# AUX_power_board_V3_2.net
KiCad netlist of a schematic drawn in EAGLE
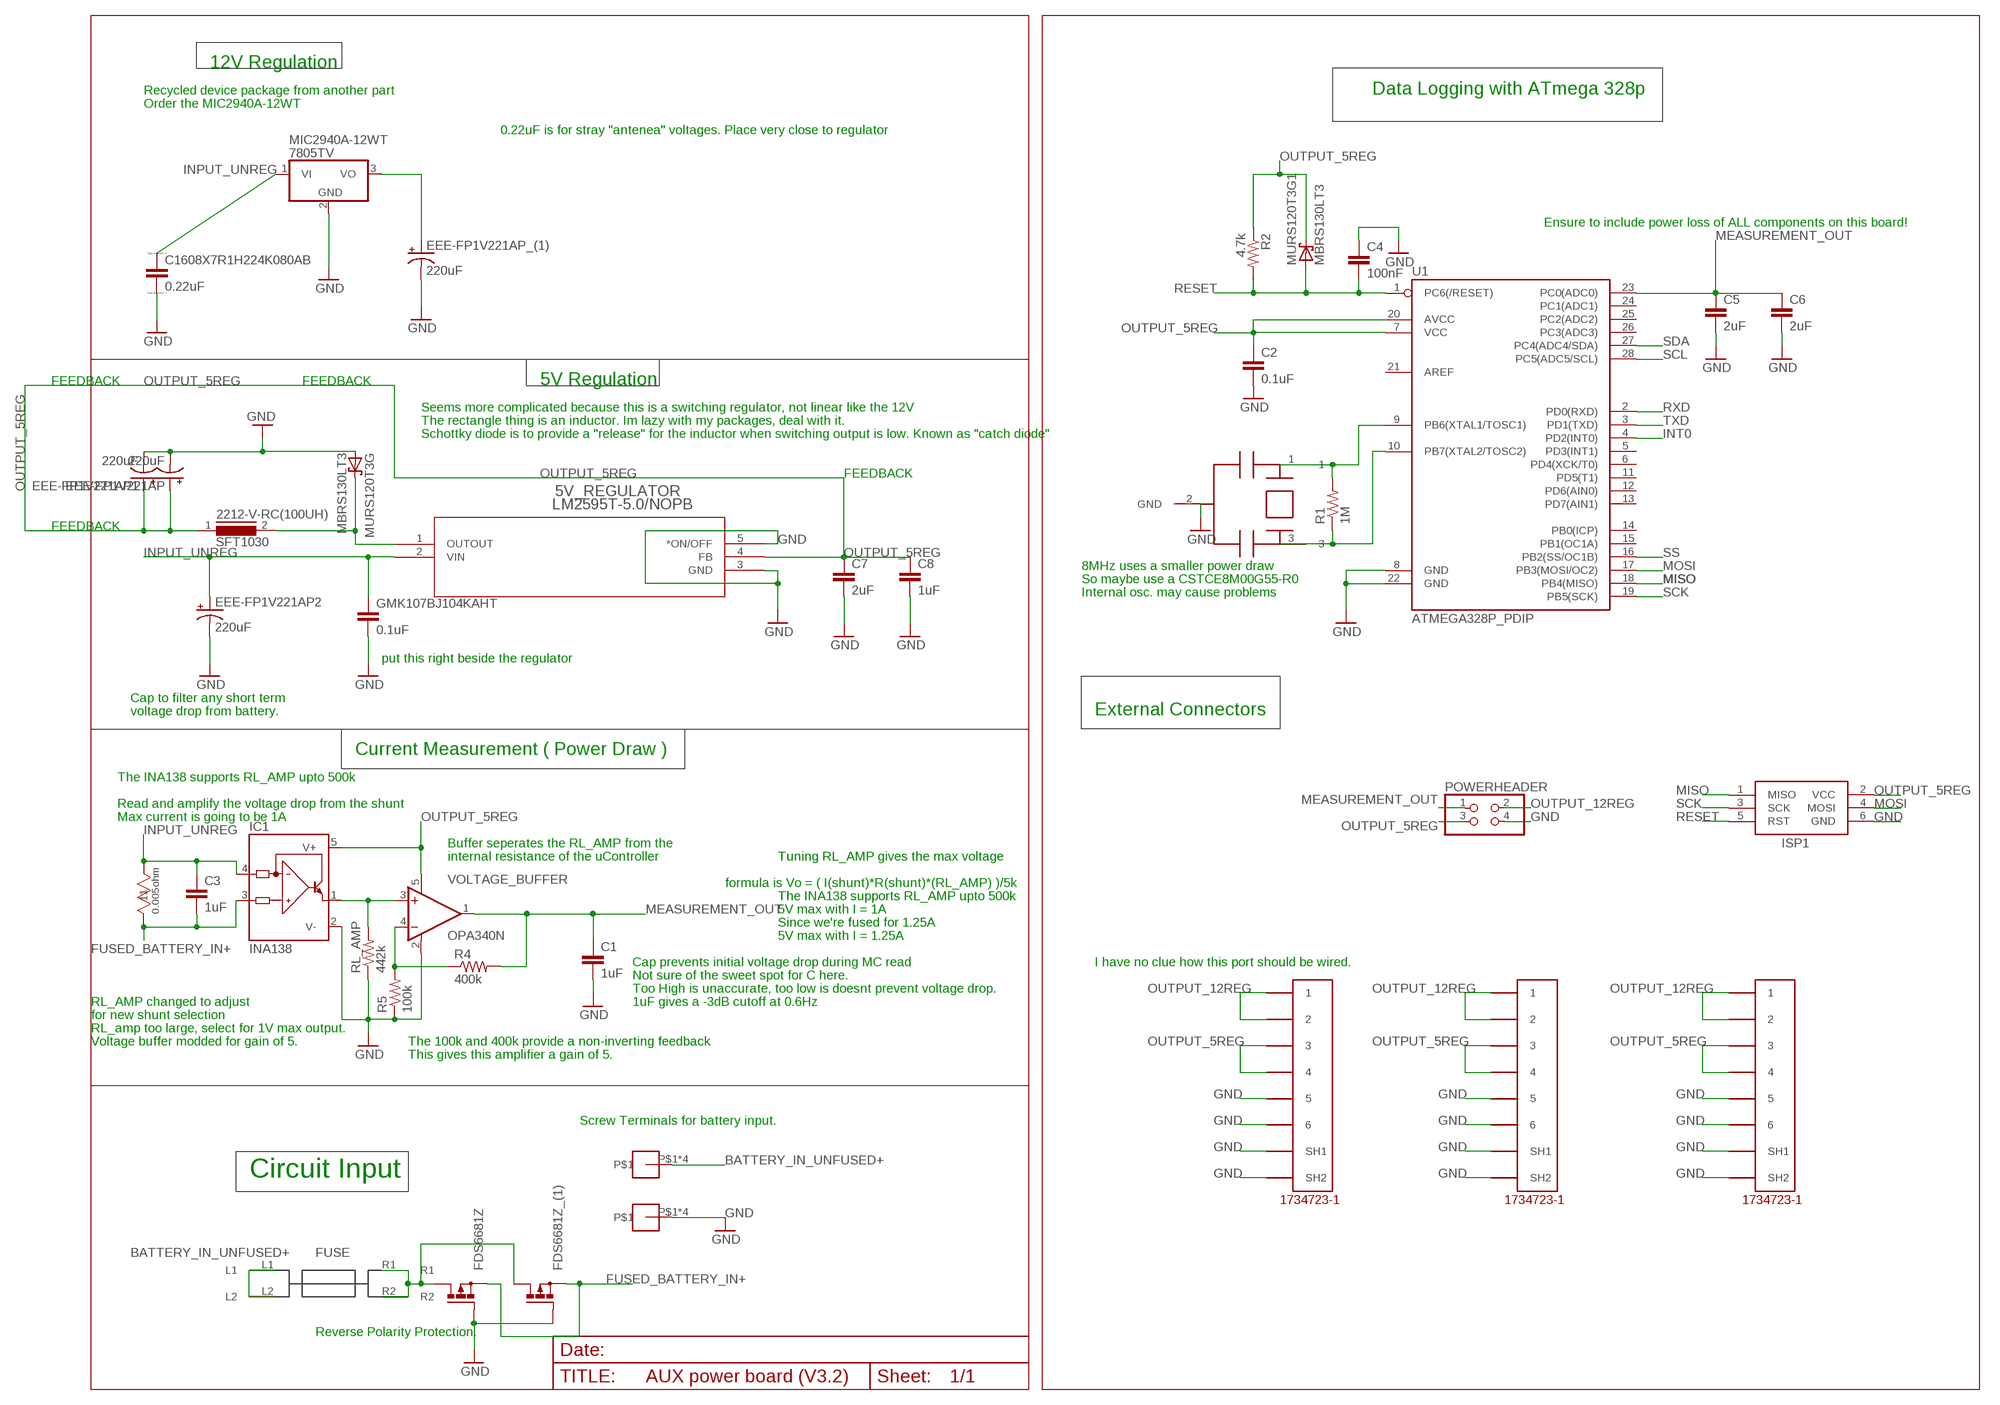
[diagram p0: schematic, sheet 1]

(export (version "E")
  (design (tool "Eeschema 10.0.6"))
  (components
    (comp (ref "5V_REGULATOR")
      (value "LM2595T-5.0/NOPB")
      (footprint "eagle-import:T05D")
      (fields
        (field (name "MANUFACTURER_PART_NUMBER") "LM2595T50")
        (field (name "COPYRIGHT") "Copyright C 2015 Accelerated Designs. All rights reserved")
      )
      (libsource (lib "eagle-import") (part "LM2595T-5.0/NOPB"))
    )
    (comp (ref "15FR005E")
      (value "15FR005E")
      (footprint "eagle-import:RES_15")
      (fields (field (name "COPYRIGHT") "Copyright C 2015 Accelerated Designs. All rights reserved"))
      (libsource (lib "eagle-import") (part "15FR005E"))
    )
    (comp (ref "2212-V-RC(100UH)")
      (value "SFT1030")
      (footprint "eagle-import:SFT1030")
      (libsource (lib "eagle-import") (part "SFT1030"))
    )
    (comp (ref "C1")
      (value "1uF")
      (footprint "eagle-import:C0603")
      (libsource (lib "eagle-import") (part "resistor_C-EUC0603"))
    )
    (comp (ref "C2")
      (value "0.1uF")
      (footprint "eagle-import:C0603")
      (libsource (lib "eagle-import") (part "resistor_C-EUC0603"))
    )
    (comp (ref "C3")
      (value "1uF")
      (footprint "eagle-import:C0603")
      (libsource (lib "eagle-import") (part "C-EUC0603"))
    )
    (comp (ref "C4")
      (value "100nF")
      (footprint "eagle-import:C0603")
      (libsource (lib "eagle-import") (part "C-EUC0603"))
    )
    (comp (ref "C5")
      (value "2uF")
      (footprint "eagle-import:C0603")
      (libsource (lib "eagle-import") (part "C-EUC0603"))
    )
    (comp (ref "C6")
      (value "2uF")
      (footprint "eagle-import:C0603")
      (libsource (lib "eagle-import") (part "C-EUC0603"))
    )
    (comp (ref "C7")
      (value "2uF")
      (footprint "eagle-import:C0603")
      (libsource (lib "eagle-import") (part "C-EUC0603"))
    )
    (comp (ref "C8")
      (value "1uF")
      (footprint "eagle-import:C0603")
      (libsource (lib "eagle-import") (part "C-EUC0603"))
    )
    (comp (ref "C1608X7R1H224K080AB")
      (value "0.22uF")
      (footprint "eagle-import:C0603")
      (libsource (lib "eagle-import") (part "CC0603"))
    )
    (comp (ref "CSTCE8M00G55-R0")
      (value "CSTCE16M0V53-R0")
      (footprint "eagle-import:RESONATOR")
      (libsource (lib "eagle-import") (part "CSTCE16M0V53-R0"))
    )
    (comp (ref "EEE-FP1V221AP")
      (value "220uF")
      (footprint "eagle-import:175TMP-0808")
      (libsource (lib "eagle-import") (part "CPOL-US175TMP-0808"))
    )
    (comp (ref "EEE-FP1V221AP1")
      (value "220uF")
      (footprint "eagle-import:175TMP-0808")
      (libsource (lib "eagle-import") (part "CPOL-US175TMP-0808"))
    )
    (comp (ref "EEE-FP1V221AP2")
      (value "220uF")
      (footprint "eagle-import:175TMP-0808")
      (libsource (lib "eagle-import") (part "CPOL-US175TMP-0808"))
    )
    (comp (ref "EEE-FP1V221AP_(1)")
      (value "220uF")
      (footprint "eagle-import:175TMP-0808")
      (libsource (lib "eagle-import") (part "CPOL-US175TMP-0808"))
    )
    (comp (ref "FDS6681Z")
      (value "P-MOSFET-SO8")
      (footprint "eagle-import:SO-08")
      (libsource (lib "eagle-import") (part "P-MOSFET-SO8"))
    )
    (comp (ref "FDS6681Z_(1)")
      (value "P-MOSFET-SO8")
      (footprint "eagle-import:SO-08")
      (libsource (lib "eagle-import") (part "P-MOSFET-SO8"))
    )
    (comp (ref "GMK107BJ104KAHT")
      (value "0.1uF")
      (footprint "eagle-import:C0603")
      (libsource (lib "eagle-import") (part "C-EUC0603"))
    )
    (comp (ref "IC1")
      (value "INA138")
      (footprint "eagle-import:SOT23-5")
      (fields (field (name "MF") "TEXAS INSTRUMENTS") (field (name "MPN") "INA138NA/250"))
      (libsource (lib "eagle-import") (part "INA138"))
    )
    (comp (ref "ISP1")
      (value "AVRISP-6")
      (footprint "eagle-import:AVRISP")
      (libsource (lib "eagle-import") (part "AVRISP-6"))
    )
    (comp (ref "MIC2940A-12WT")
      (value "7805TV")
      (footprint "eagle-import:TO220V")
      (libsource (lib "eagle-import") (part "78TV05"))
    )
    (comp (ref "MINIBLADE")
      (value "3568")
      (footprint "eagle-import:3568")
      (libsource (lib "eagle-import") (part "3568"))
    )
    (comp (ref "MURS120T3G")
      (value "MBRS130LT3")
      (footprint "eagle-import:SMB")
      (libsource (lib "eagle-import") (part "MBRS130LT3"))
    )
    (comp (ref "MURS120T3G1")
      (value "MBRS130LT3")
      (footprint "eagle-import:SMB")
      (libsource (lib "eagle-import") (part "MBRS130LT3"))
    )
    (comp (ref "POWERHEADER")
      (value "PINHD-2X2")
      (footprint "eagle-import:2X02")
      (libsource (lib "eagle-import") (part "PINHD-2X2"))
    )
    (comp (ref "R1")
      (value "1M")
      (footprint "eagle-import:R0603")
      (libsource (lib "eagle-import") (part "R-US_R0603"))
    )
    (comp (ref "R2")
      (value "4.7k")
      (footprint "eagle-import:R0603")
      (libsource (lib "eagle-import") (part "resistor_R-US_R0603"))
    )
    (comp (ref "R4")
      (value "400k")
      (footprint "eagle-import:R0603")
      (libsource (lib "eagle-import") (part "resistor_R-US_R0603"))
    )
    (comp (ref "R5")
      (value "100k")
      (footprint "eagle-import:R0603")
      (libsource (lib "eagle-import") (part "resistor_R-US_R0603"))
    )
    (comp (ref "RL_AMP")
      (value "442k")
      (footprint "eagle-import:R0603")
      (libsource (lib "eagle-import") (part "resistor_R-US_R0603"))
    )
    (comp (ref "U$3")
      (value "5555140-6")
      (footprint "eagle-import:1734723-1_RJ11")
      (libsource (lib "eagle-import") (part "5555140-6"))
    )
    (comp (ref "U$4")
      (value "5555140-6")
      (footprint "eagle-import:1734723-1_RJ11")
      (libsource (lib "eagle-import") (part "5555140-6"))
    )
    (comp (ref "U$5")
      (value "5555140-6")
      (footprint "eagle-import:1734723-1_RJ11")
      (libsource (lib "eagle-import") (part "5555140-6"))
    )
    (comp (ref "U$6")
      (value "SCREW-8191")
      (footprint "eagle-import:SCREW-8191")
      (libsource (lib "eagle-import") (part "SCREW-8191"))
    )
    (comp (ref "U$7")
      (value "SCREW-8191")
      (footprint "eagle-import:SCREW-8191")
      (libsource (lib "eagle-import") (part "SCREW-8191"))
    )
    (comp (ref "U1")
      (value "ATMEGA328P_PDIP")
      (footprint "eagle-import:DIL28-3")
      (libsource (lib "eagle-import") (part "ATMEGA328P_PDIP"))
    )
    (comp (ref "VOLTAGE_BUFFER")
      (value "OPA340N")
      (footprint "eagle-import:SOT23-5")
      (fields (field (name "MPN") "OPA340NA/3KG4"))
      (libsource (lib "eagle-import") (part "OPA340N"))
    )
  )
  (nets
    (net (code "1") (name "/BATTERY_IN_UNFUSED+") (class "Default")
      (node (ref "MINIBLADE") (pin "L1") (pinfunction "L1_L1") (pintype "bidirectional"))
      (node (ref "MINIBLADE") (pin "L2") (pinfunction "L2_L2") (pintype "bidirectional"))
      (node (ref "U$6") (pin "P$1") (pinfunction "P$1_P$1") (pintype "bidirectional"))
      (node (ref "U$6") (pin "P$2") (pinfunction "P$1_P$2") (pintype "bidirectional"))
      (node (ref "U$6") (pin "P$3") (pinfunction "P$1_P$3") (pintype "bidirectional"))
      (node (ref "U$6") (pin "P$4") (pinfunction "P$1_P$4") (pintype "bidirectional"))
    )
    (net (code "2") (name "/FUSED_BATTERY_IN+") (class "Default")
      (node (ref "15FR005E") (pin "1") (pinfunction "11_1") (pintype "passive"))
      (node (ref "C3") (pin "2") (pinfunction "2_2") (pintype "passive"))
      (node (ref "FDS6681Z") (pin "1") (pinfunction "S_1") (pintype "passive"))
      (node (ref "FDS6681Z") (pin "2") (pinfunction "S_2") (pintype "passive"))
      (node (ref "FDS6681Z") (pin "3") (pinfunction "S_3") (pintype "passive"))
      (node (ref "FDS6681Z_(1)") (pin "1") (pinfunction "S_1") (pintype "passive"))
      (node (ref "FDS6681Z_(1)") (pin "2") (pinfunction "S_2") (pintype "passive"))
      (node (ref "FDS6681Z_(1)") (pin "3") (pinfunction "S_3") (pintype "passive"))
      (node (ref "IC1") (pin "3") (pinfunction "IN+_3") (pintype "input"))
    )
    (net (code "3") (name "/INPUT_UNREG") (class "Default")
      (node (ref "15FR005E") (pin "2") (pinfunction "22_2") (pintype "passive"))
      (node (ref "5V_REGULATOR") (pin "2") (pinfunction "VIN_2") (pintype "input"))
      (node (ref "C1608X7R1H224K080AB") (pin "1") (pinfunction "1_1") (pintype "passive"))
      (node (ref "C3") (pin "1") (pinfunction "1_1") (pintype "passive"))
      (node (ref "EEE-FP1V221AP2") (pin "+") (pinfunction "+_+") (pintype "passive"))
      (node (ref "GMK107BJ104KAHT") (pin "1") (pinfunction "1_1") (pintype "passive"))
      (node (ref "IC1") (pin "4") (pinfunction "IN-_4") (pintype "input"))
      (node (ref "MIC2940A-12WT") (pin "1") (pinfunction "VI_1") (pintype "input"))
    )
    (net (code "4") (name "/INT0") (class "Default")
      (node (ref "U1") (pin "4") (pinfunction "PD2(INT0)_4") (pintype "bidirectional"))
    )
    (net (code "5") (name "/MEASUREMENT_OUT") (class "Default")
      (node (ref "C1") (pin "1") (pinfunction "1_1") (pintype "passive"))
      (node (ref "C5") (pin "1") (pinfunction "1_1") (pintype "passive"))
      (node (ref "C6") (pin "1") (pinfunction "1_1") (pintype "passive"))
      (node (ref "POWERHEADER") (pin "1") (pinfunction "1_1") (pintype "passive"))
      (node (ref "R4") (pin "2") (pinfunction "2_2") (pintype "passive"))
      (node (ref "U1") (pin "23") (pinfunction "PC0(ADC0)_23") (pintype "bidirectional"))
      (node (ref "VOLTAGE_BUFFER") (pin "1") (pinfunction "OUT_1") (pintype "output"))
    )
    (net (code "6") (name "/MISO") (class "Default")
      (node (ref "ISP1") (pin "1") (pinfunction "MISO_1") (pintype "input"))
      (node (ref "U1") (pin "18") (pinfunction "PB4(MISO)_18") (pintype "bidirectional"))
    )
    (net (code "7") (name "/MOSI") (class "Default")
      (node (ref "ISP1") (pin "4") (pinfunction "MOSI_4") (pintype "output"))
      (node (ref "U1") (pin "17") (pinfunction "PB3(MOSI/OC2)_17") (pintype "bidirectional"))
    )
    (net (code "8") (name "/OUTPUT_5REG") (class "Default")
      (node (ref "2212-V-RC(100UH)") (pin "1") (pinfunction "1_1") (pintype "passive"))
      (node (ref "5V_REGULATOR") (pin "4") (pinfunction "FB_4") (pintype "passive"))
      (node (ref "C2") (pin "1") (pinfunction "1_1") (pintype "passive"))
      (node (ref "C7") (pin "1") (pinfunction "1_1") (pintype "passive"))
      (node (ref "C8") (pin "1") (pinfunction "1_1") (pintype "passive"))
      (node (ref "EEE-FP1V221AP") (pin "+") (pinfunction "+_+") (pintype "passive"))
      (node (ref "EEE-FP1V221AP1") (pin "+") (pinfunction "+_+") (pintype "passive"))
      (node (ref "IC1") (pin "5") (pinfunction "V+_5") (pintype "power_in"))
      (node (ref "ISP1") (pin "2") (pinfunction "VCC_2") (pintype "power_in"))
      (node (ref "MURS120T3G1") (pin "C") (pinfunction "C_C") (pintype "passive"))
      (node (ref "POWERHEADER") (pin "3") (pinfunction "3_3") (pintype "passive"))
      (node (ref "R2") (pin "1") (pinfunction "1_1") (pintype "passive"))
      (node (ref "U$3") (pin "3") (pinfunction "3_3") (pintype "bidirectional"))
      (node (ref "U$3") (pin "4") (pinfunction "4_4") (pintype "bidirectional"))
      (node (ref "U$4") (pin "3") (pinfunction "3_3") (pintype "bidirectional"))
      (node (ref "U$4") (pin "4") (pinfunction "4_4") (pintype "bidirectional"))
      (node (ref "U$5") (pin "3") (pinfunction "3_3") (pintype "bidirectional"))
      (node (ref "U$5") (pin "4") (pinfunction "4_4") (pintype "bidirectional"))
      (node (ref "U1") (pin "20") (pinfunction "AVCC_20") (pintype "bidirectional"))
      (node (ref "U1") (pin "7") (pinfunction "VCC_7") (pintype "bidirectional"))
      (node (ref "VOLTAGE_BUFFER") (pin "5") (pinfunction "V+_5") (pintype "power_in"))
    )
    (net (code "9") (name "/OUTPUT_12REG") (class "Default")
      (node (ref "EEE-FP1V221AP_(1)") (pin "+") (pinfunction "+_+") (pintype "passive"))
      (node (ref "MIC2940A-12WT") (pin "3") (pinfunction "VO_3") (pintype "passive"))
      (node (ref "POWERHEADER") (pin "2") (pinfunction "2_2") (pintype "passive"))
      (node (ref "U$3") (pin "1") (pinfunction "1_1") (pintype "bidirectional"))
      (node (ref "U$3") (pin "2") (pinfunction "2_2") (pintype "bidirectional"))
      (node (ref "U$4") (pin "1") (pinfunction "1_1") (pintype "bidirectional"))
      (node (ref "U$4") (pin "2") (pinfunction "2_2") (pintype "bidirectional"))
      (node (ref "U$5") (pin "1") (pinfunction "1_1") (pintype "bidirectional"))
      (node (ref "U$5") (pin "2") (pinfunction "2_2") (pintype "bidirectional"))
    )
    (net (code "10") (name "/RESET") (class "Default")
      (node (ref "C4") (pin "2") (pinfunction "2_2") (pintype "passive"))
      (node (ref "ISP1") (pin "5") (pinfunction "RST_5") (pintype "output"))
      (node (ref "MURS120T3G1") (pin "A") (pinfunction "A_A") (pintype "passive"))
      (node (ref "R2") (pin "2") (pinfunction "2_2") (pintype "passive"))
      (node (ref "U1") (pin "1") (pinfunction "PC6(/RESET)_1") (pintype "bidirectional"))
    )
    (net (code "11") (name "/RXD") (class "Default")
      (node (ref "U1") (pin "2") (pinfunction "PD0(RXD)_2") (pintype "bidirectional"))
    )
    (net (code "12") (name "/SCK") (class "Default")
      (node (ref "ISP1") (pin "3") (pinfunction "SCK_3") (pintype "output"))
      (node (ref "U1") (pin "19") (pinfunction "PB5(SCK)_19") (pintype "bidirectional"))
    )
    (net (code "13") (name "/SCL") (class "Default")
      (node (ref "U1") (pin "28") (pinfunction "PC5(ADC5/SCL)_28") (pintype "bidirectional"))
    )
    (net (code "14") (name "/SDA") (class "Default")
      (node (ref "U1") (pin "27") (pinfunction "PC4(ADC4/SDA)_27") (pintype "bidirectional"))
    )
    (net (code "15") (name "/SS") (class "Default")
      (node (ref "U1") (pin "16") (pinfunction "PB2(SS/OC1B)_16") (pintype "bidirectional"))
    )
    (net (code "16") (name "/TXD") (class "Default")
      (node (ref "U1") (pin "3") (pinfunction "PD1(TXD)_3") (pintype "bidirectional"))
    )
    (net (code "17") (name "GND") (class "Default")
      (node (ref "5V_REGULATOR") (pin "3") (pinfunction "GND_3") (pintype "passive"))
      (node (ref "5V_REGULATOR") (pin "5") (pinfunction "*ON/OFF_5") (pintype "passive"))
      (node (ref "C1") (pin "2") (pinfunction "2_2") (pintype "passive"))
      (node (ref "C1608X7R1H224K080AB") (pin "2") (pinfunction "2_2") (pintype "passive"))
      (node (ref "C2") (pin "2") (pinfunction "2_2") (pintype "passive"))
      (node (ref "C4") (pin "1") (pinfunction "1_1") (pintype "passive"))
      (node (ref "C5") (pin "2") (pinfunction "2_2") (pintype "passive"))
      (node (ref "C6") (pin "2") (pinfunction "2_2") (pintype "passive"))
      (node (ref "C7") (pin "2") (pinfunction "2_2") (pintype "passive"))
      (node (ref "C8") (pin "2") (pinfunction "2_2") (pintype "passive"))
      (node (ref "CSTCE8M00G55-R0") (pin "2") (pinfunction "GND_2") (pintype "bidirectional"))
      (node (ref "EEE-FP1V221AP") (pin "-") (pinfunction "-_-") (pintype "passive"))
      (node (ref "EEE-FP1V221AP1") (pin "-") (pinfunction "-_-") (pintype "passive"))
      (node (ref "EEE-FP1V221AP2") (pin "-") (pinfunction "-_-") (pintype "passive"))
      (node (ref "EEE-FP1V221AP_(1)") (pin "-") (pinfunction "-_-") (pintype "passive"))
      (node (ref "FDS6681Z") (pin "4") (pinfunction "G_4") (pintype "passive"))
      (node (ref "FDS6681Z_(1)") (pin "4") (pinfunction "G_4") (pintype "passive"))
      (node (ref "GMK107BJ104KAHT") (pin "2") (pinfunction "2_2") (pintype "passive"))
      (node (ref "IC1") (pin "2") (pinfunction "V-_2") (pintype "power_in"))
      (node (ref "ISP1") (pin "6") (pinfunction "GND_6") (pintype "power_in"))
      (node (ref "MIC2940A-12WT") (pin "2") (pinfunction "GND_2") (pintype "passive"))
      (node (ref "MURS120T3G") (pin "A") (pinfunction "A_A") (pintype "passive"))
      (node (ref "POWERHEADER") (pin "4") (pinfunction "4_4") (pintype "passive"))
      (node (ref "R5") (pin "1") (pinfunction "1_1") (pintype "passive"))
      (node (ref "RL_AMP") (pin "1") (pinfunction "1_1") (pintype "passive"))
      (node (ref "U$3") (pin "5") (pinfunction "5_5") (pintype "bidirectional"))
      (node (ref "U$3") (pin "6") (pinfunction "6_6") (pintype "bidirectional"))
      (node (ref "U$3") (pin "SH1") (pinfunction "SH1_SH1") (pintype "bidirectional"))
      (node (ref "U$3") (pin "SH2") (pinfunction "SH2_SH2") (pintype "bidirectional"))
      (node (ref "U$4") (pin "5") (pinfunction "5_5") (pintype "bidirectional"))
      (node (ref "U$4") (pin "6") (pinfunction "6_6") (pintype "bidirectional"))
      (node (ref "U$4") (pin "SH1") (pinfunction "SH1_SH1") (pintype "bidirectional"))
      (node (ref "U$4") (pin "SH2") (pinfunction "SH2_SH2") (pintype "bidirectional"))
      (node (ref "U$5") (pin "5") (pinfunction "5_5") (pintype "bidirectional"))
      (node (ref "U$5") (pin "6") (pinfunction "6_6") (pintype "bidirectional"))
      (node (ref "U$5") (pin "SH1") (pinfunction "SH1_SH1") (pintype "bidirectional"))
      (node (ref "U$5") (pin "SH2") (pinfunction "SH2_SH2") (pintype "bidirectional"))
      (node (ref "U$7") (pin "P$1") (pinfunction "P$1_P$1") (pintype "bidirectional"))
      (node (ref "U$7") (pin "P$2") (pinfunction "P$1_P$2") (pintype "bidirectional"))
      (node (ref "U$7") (pin "P$3") (pinfunction "P$1_P$3") (pintype "bidirectional"))
      (node (ref "U$7") (pin "P$4") (pinfunction "P$1_P$4") (pintype "bidirectional"))
      (node (ref "U1") (pin "22") (pinfunction "GND_22") (pintype "bidirectional"))
      (node (ref "U1") (pin "8") (pinfunction "GND_8") (pintype "bidirectional"))
      (node (ref "VOLTAGE_BUFFER") (pin "2") (pinfunction "V-_2") (pintype "power_in"))
    )
    (net (code "18") (name "Net-(5V_REGULATOR-OUTOUT)") (class "Default")
      (node (ref "2212-V-RC(100UH)") (pin "2") (pinfunction "2_2") (pintype "passive"))
      (node (ref "5V_REGULATOR") (pin "1") (pinfunction "OUTOUT_1") (pintype "output"))
      (node (ref "MURS120T3G") (pin "C") (pinfunction "C_C") (pintype "passive"))
    )
    (net (code "19") (name "Net-(FDS6681Z-D-Pad5)") (class "Default")
      (node (ref "FDS6681Z") (pin "5") (pinfunction "D_5") (pintype "passive"))
      (node (ref "FDS6681Z") (pin "6") (pinfunction "D_6") (pintype "passive"))
      (node (ref "FDS6681Z") (pin "7") (pinfunction "D_7") (pintype "passive"))
      (node (ref "FDS6681Z") (pin "8") (pinfunction "D_8") (pintype "passive"))
      (node (ref "FDS6681Z_(1)") (pin "5") (pinfunction "D_5") (pintype "passive"))
      (node (ref "FDS6681Z_(1)") (pin "6") (pinfunction "D_6") (pintype "passive"))
      (node (ref "FDS6681Z_(1)") (pin "7") (pinfunction "D_7") (pintype "passive"))
      (node (ref "FDS6681Z_(1)") (pin "8") (pinfunction "D_8") (pintype "passive"))
      (node (ref "MINIBLADE") (pin "R1") (pinfunction "R1_R1") (pintype "bidirectional"))
      (node (ref "MINIBLADE") (pin "R2") (pinfunction "R2_R2") (pintype "bidirectional"))
    )
    (net (code "20") (name "Net-(IC1-OUT)") (class "Default")
      (node (ref "IC1") (pin "1") (pinfunction "OUT_1") (pintype "output"))
      (node (ref "RL_AMP") (pin "2") (pinfunction "2_2") (pintype "passive"))
      (node (ref "VOLTAGE_BUFFER") (pin "3") (pinfunction "+IN_3") (pintype "input"))
    )
    (net (code "21") (name "Net-(U1-PB6(XTAL1{slash}TOSC1))") (class "Default")
      (node (ref "CSTCE8M00G55-R0") (pin "1") (pinfunction "1_1") (pintype "bidirectional"))
      (node (ref "R1") (pin "2") (pinfunction "2_2") (pintype "passive"))
      (node (ref "U1") (pin "9") (pinfunction "PB6(XTAL1/TOSC1)_9") (pintype "bidirectional"))
    )
    (net (code "22") (name "Net-(U1-PB7(XTAL2{slash}TOSC2))") (class "Default")
      (node (ref "CSTCE8M00G55-R0") (pin "3") (pinfunction "3_3") (pintype "bidirectional"))
      (node (ref "R1") (pin "1") (pinfunction "1_1") (pintype "passive"))
      (node (ref "U1") (pin "10") (pinfunction "PB7(XTAL2/TOSC2)_10") (pintype "bidirectional"))
    )
    (net (code "23") (name "Net-(VOLTAGE_BUFFER--IN)") (class "Default")
      (node (ref "R4") (pin "1") (pinfunction "1_1") (pintype "passive"))
      (node (ref "R5") (pin "2") (pinfunction "2_2") (pintype "passive"))
      (node (ref "VOLTAGE_BUFFER") (pin "4") (pinfunction "-IN_4") (pintype "input"))
    )
    (net (code "24") (name "unconnected-(U1-AREF-Pad21)") (class "Default")
      (node (ref "U1") (pin "21") (pinfunction "AREF_21") (pintype "bidirectional"))
    )
    (net (code "25") (name "unconnected-(U1-PB0(ICP)-Pad14)") (class "Default")
      (node (ref "U1") (pin "14") (pinfunction "PB0(ICP)_14") (pintype "bidirectional"))
    )
    (net (code "26") (name "unconnected-(U1-PB1(OC1A)-Pad15)") (class "Default")
      (node (ref "U1") (pin "15") (pinfunction "PB1(OC1A)_15") (pintype "bidirectional"))
    )
    (net (code "27") (name "unconnected-(U1-PC1(ADC1)-Pad24)") (class "Default")
      (node (ref "U1") (pin "24") (pinfunction "PC1(ADC1)_24") (pintype "bidirectional"))
    )
    (net (code "28") (name "unconnected-(U1-PC2(ADC2)-Pad25)") (class "Default")
      (node (ref "U1") (pin "25") (pinfunction "PC2(ADC2)_25") (pintype "bidirectional"))
    )
    (net (code "29") (name "unconnected-(U1-PC3(ADC3)-Pad26)") (class "Default")
      (node (ref "U1") (pin "26") (pinfunction "PC3(ADC3)_26") (pintype "bidirectional"))
    )
    (net (code "30") (name "unconnected-(U1-PD3(INT1)-Pad5)") (class "Default")
      (node (ref "U1") (pin "5") (pinfunction "PD3(INT1)_5") (pintype "bidirectional"))
    )
    (net (code "31") (name "unconnected-(U1-PD4(XCK{slash}T0)-Pad6)") (class "Default")
      (node (ref "U1") (pin "6") (pinfunction "PD4(XCK/T0)_6") (pintype "bidirectional"))
    )
    (net (code "32") (name "unconnected-(U1-PD5(T1)-Pad11)") (class "Default")
      (node (ref "U1") (pin "11") (pinfunction "PD5(T1)_11") (pintype "bidirectional"))
    )
    (net (code "33") (name "unconnected-(U1-PD6(AIN0)-Pad12)") (class "Default")
      (node (ref "U1") (pin "12") (pinfunction "PD6(AIN0)_12") (pintype "bidirectional"))
    )
    (net (code "34") (name "unconnected-(U1-PD7(AIN1)-Pad13)") (class "Default")
      (node (ref "U1") (pin "13") (pinfunction "PD7(AIN1)_13") (pintype "bidirectional"))
    )
  )
)
